# rgb.net
KiCad netlist of a schematic drawn in Altium Designer
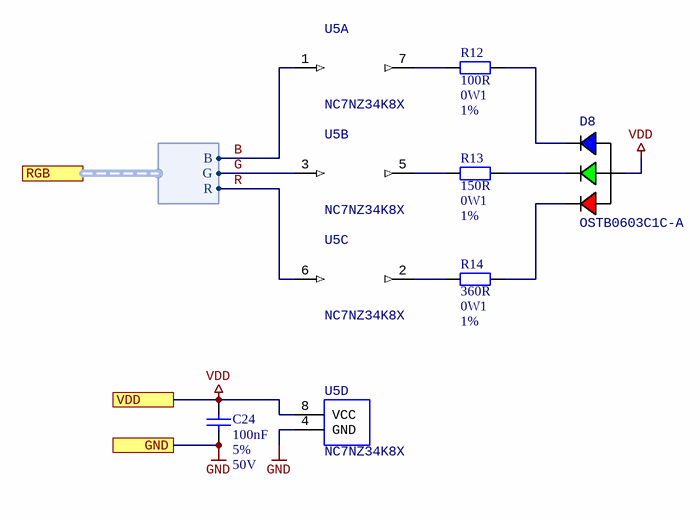
[diagram p0: rgb.SchDoc]

(export (version "E")
  (design (tool "Eeschema 10.0.6"))
  (components
    (comp (ref "C24")
      (value "100nF")
      (footprint "CAPC1608N")
      (description "Capacitor")
      (fields (field (name "TOLERANCE") "5%") (field (name "VOLTAGE") "50V"))
      (libsource (lib "passives") (part "Capacitor"))
    )
    (comp (ref "D8")
      (value "OSTB0603C1C-A")
      (footprint "RGB-0603")
      (libsource (lib "semicon") (part "RGB0603"))
    )
    (comp (ref "R12")
      (value "100R")
      (footprint "RESC1608N")
      (description "Resistor")
      (fields (field (name "POWER") "0W1") (field (name "TOLERANCE") "1%"))
      (libsource (lib "passives") (part "Resistor"))
    )
    (comp (ref "R13")
      (value "150R")
      (footprint "RESC1608N")
      (description "Resistor")
      (fields (field (name "POWER") "0W1") (field (name "TOLERANCE") "1%"))
      (libsource (lib "passives") (part "Resistor"))
    )
    (comp (ref "R14")
      (value "360R")
      (footprint "RESC1608N")
      (description "Resistor")
      (fields (field (name "POWER") "0W1") (field (name "TOLERANCE") "1%"))
      (libsource (lib "passives") (part "Resistor"))
    )
    (comp (ref "U5")
      (value "NC7NZ34K8X")
      (footprint "US8")
      (description "Trible buffer")
      (libsource (lib "logic") (part "NC7NZ34"))
    )
  )
  (nets
    (net (code "2") (name "/B") (class "Default")
      (node (ref "U5") (pin "1") (pinfunction "1A_1") (pintype "input"))
    )
    (net (code "3") (name "/G") (class "Default")
      (node (ref "U5") (pin "3") (pinfunction "2A_3") (pintype "input"))
    )
    (net (code "4") (name "/R") (class "Default")
      (node (ref "U5") (pin "6") (pinfunction "3A_6") (pintype "input"))
    )
    (net (code "6") (name "GND") (class "Default")
      (node (ref "C24") (pin "2") (pinfunction "2_2") (pintype "passive"))
      (node (ref "U5") (pin "4") (pinfunction "GND_4") (pintype "power_in"))
    )
    (net (code "7") (name "Net-(D8-KBLU)") (class "Default")
      (node (ref "D8") (pin "3") (pinfunction "KBLU_3") (pintype "passive"))
      (node (ref "R12") (pin "1") (pinfunction "1_1") (pintype "passive"))
    )
    (net (code "8") (name "Net-(D8-KGRN)") (class "Default")
      (node (ref "D8") (pin "4") (pinfunction "KGRN_4") (pintype "passive"))
      (node (ref "R13") (pin "1") (pinfunction "1_1") (pintype "passive"))
    )
    (net (code "9") (name "Net-(D8-KRED)") (class "Default")
      (node (ref "D8") (pin "2") (pinfunction "KRED_2") (pintype "passive"))
      (node (ref "R14") (pin "1") (pinfunction "1_1") (pintype "passive"))
    )
    (net (code "10") (name "Net-(U5A-1Y)") (class "Default")
      (node (ref "R12") (pin "2") (pinfunction "2_2") (pintype "passive"))
      (node (ref "U5") (pin "7") (pinfunction "1Y_7") (pintype "output"))
    )
    (net (code "11") (name "Net-(U5B-2Y)") (class "Default")
      (node (ref "R13") (pin "2") (pinfunction "2_2") (pintype "passive"))
      (node (ref "U5") (pin "5") (pinfunction "2Y_5") (pintype "output"))
    )
    (net (code "12") (name "Net-(U5C-3Y)") (class "Default")
      (node (ref "R14") (pin "2") (pinfunction "2_2") (pintype "passive"))
      (node (ref "U5") (pin "2") (pinfunction "3Y_2") (pintype "output"))
    )
    (net (code "13") (name "VDD") (class "Default")
      (node (ref "C24") (pin "1") (pinfunction "1_1") (pintype "passive"))
      (node (ref "D8") (pin "1") (pinfunction "A_1") (pintype "passive"))
      (node (ref "U5") (pin "8") (pinfunction "VCC_8") (pintype "power_in"))
    )
  )
)
